# P1.net
KiCad netlist of a schematic drawn in Altium Designer
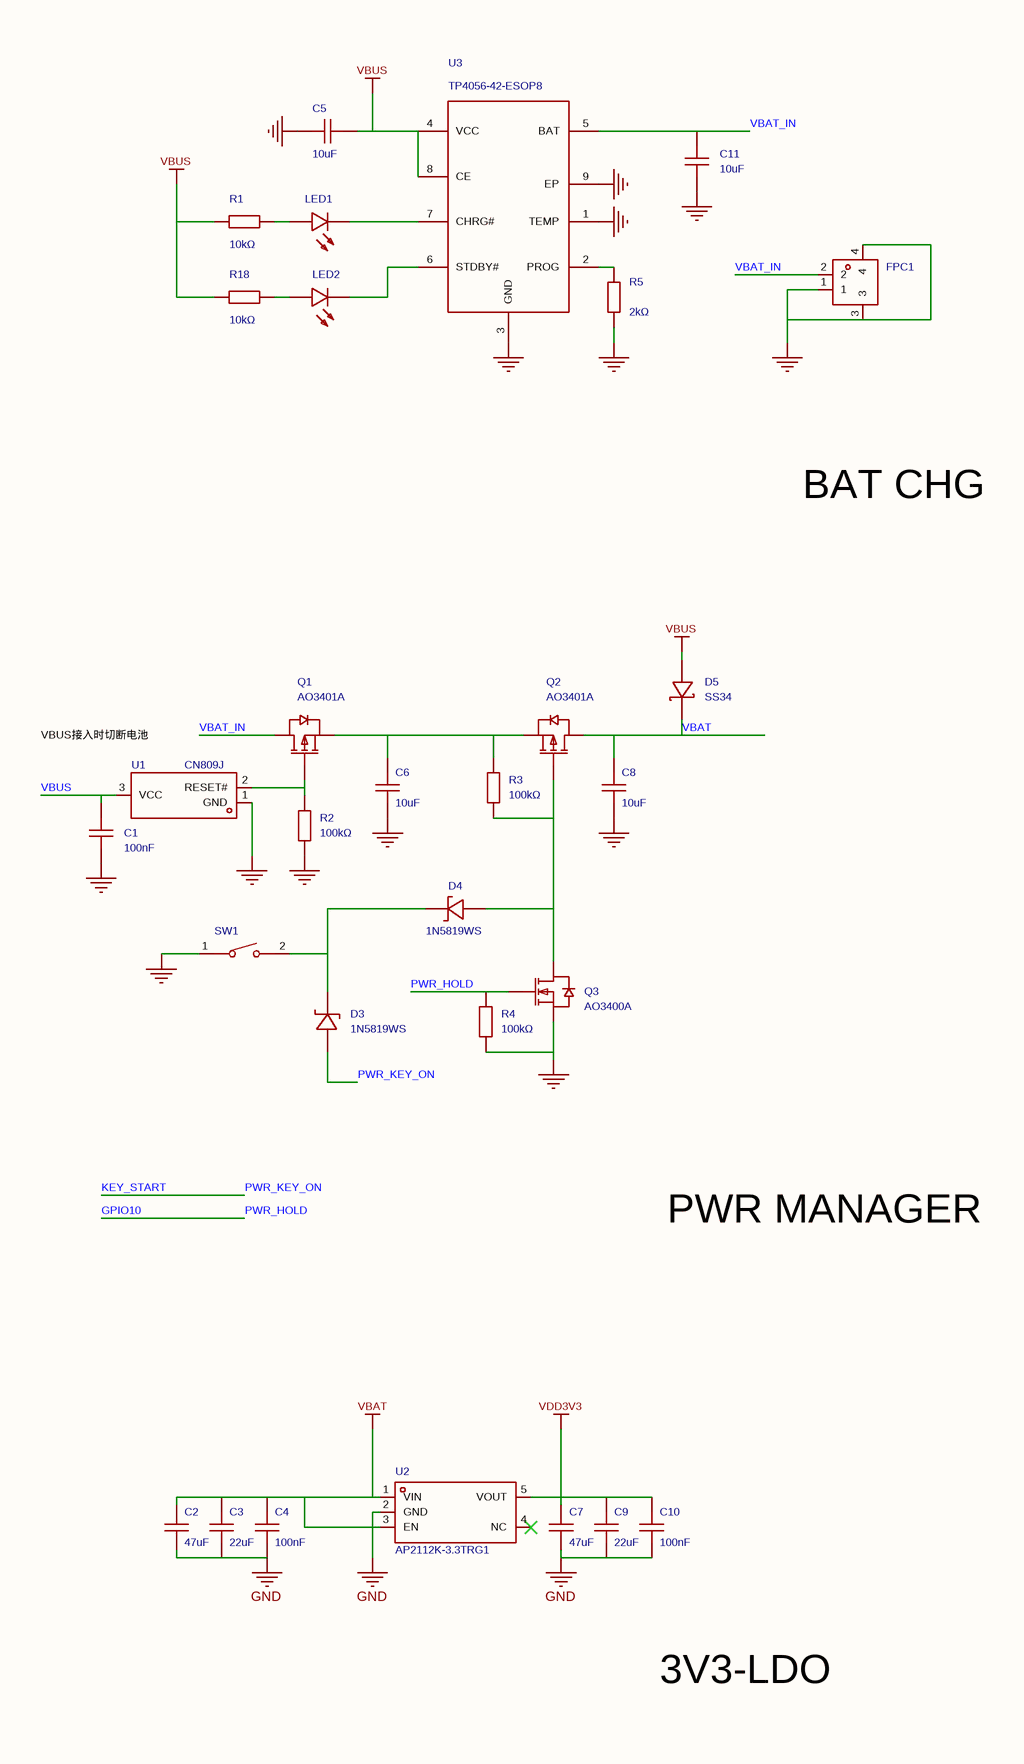
[diagram p0: P1.schdoc, left]
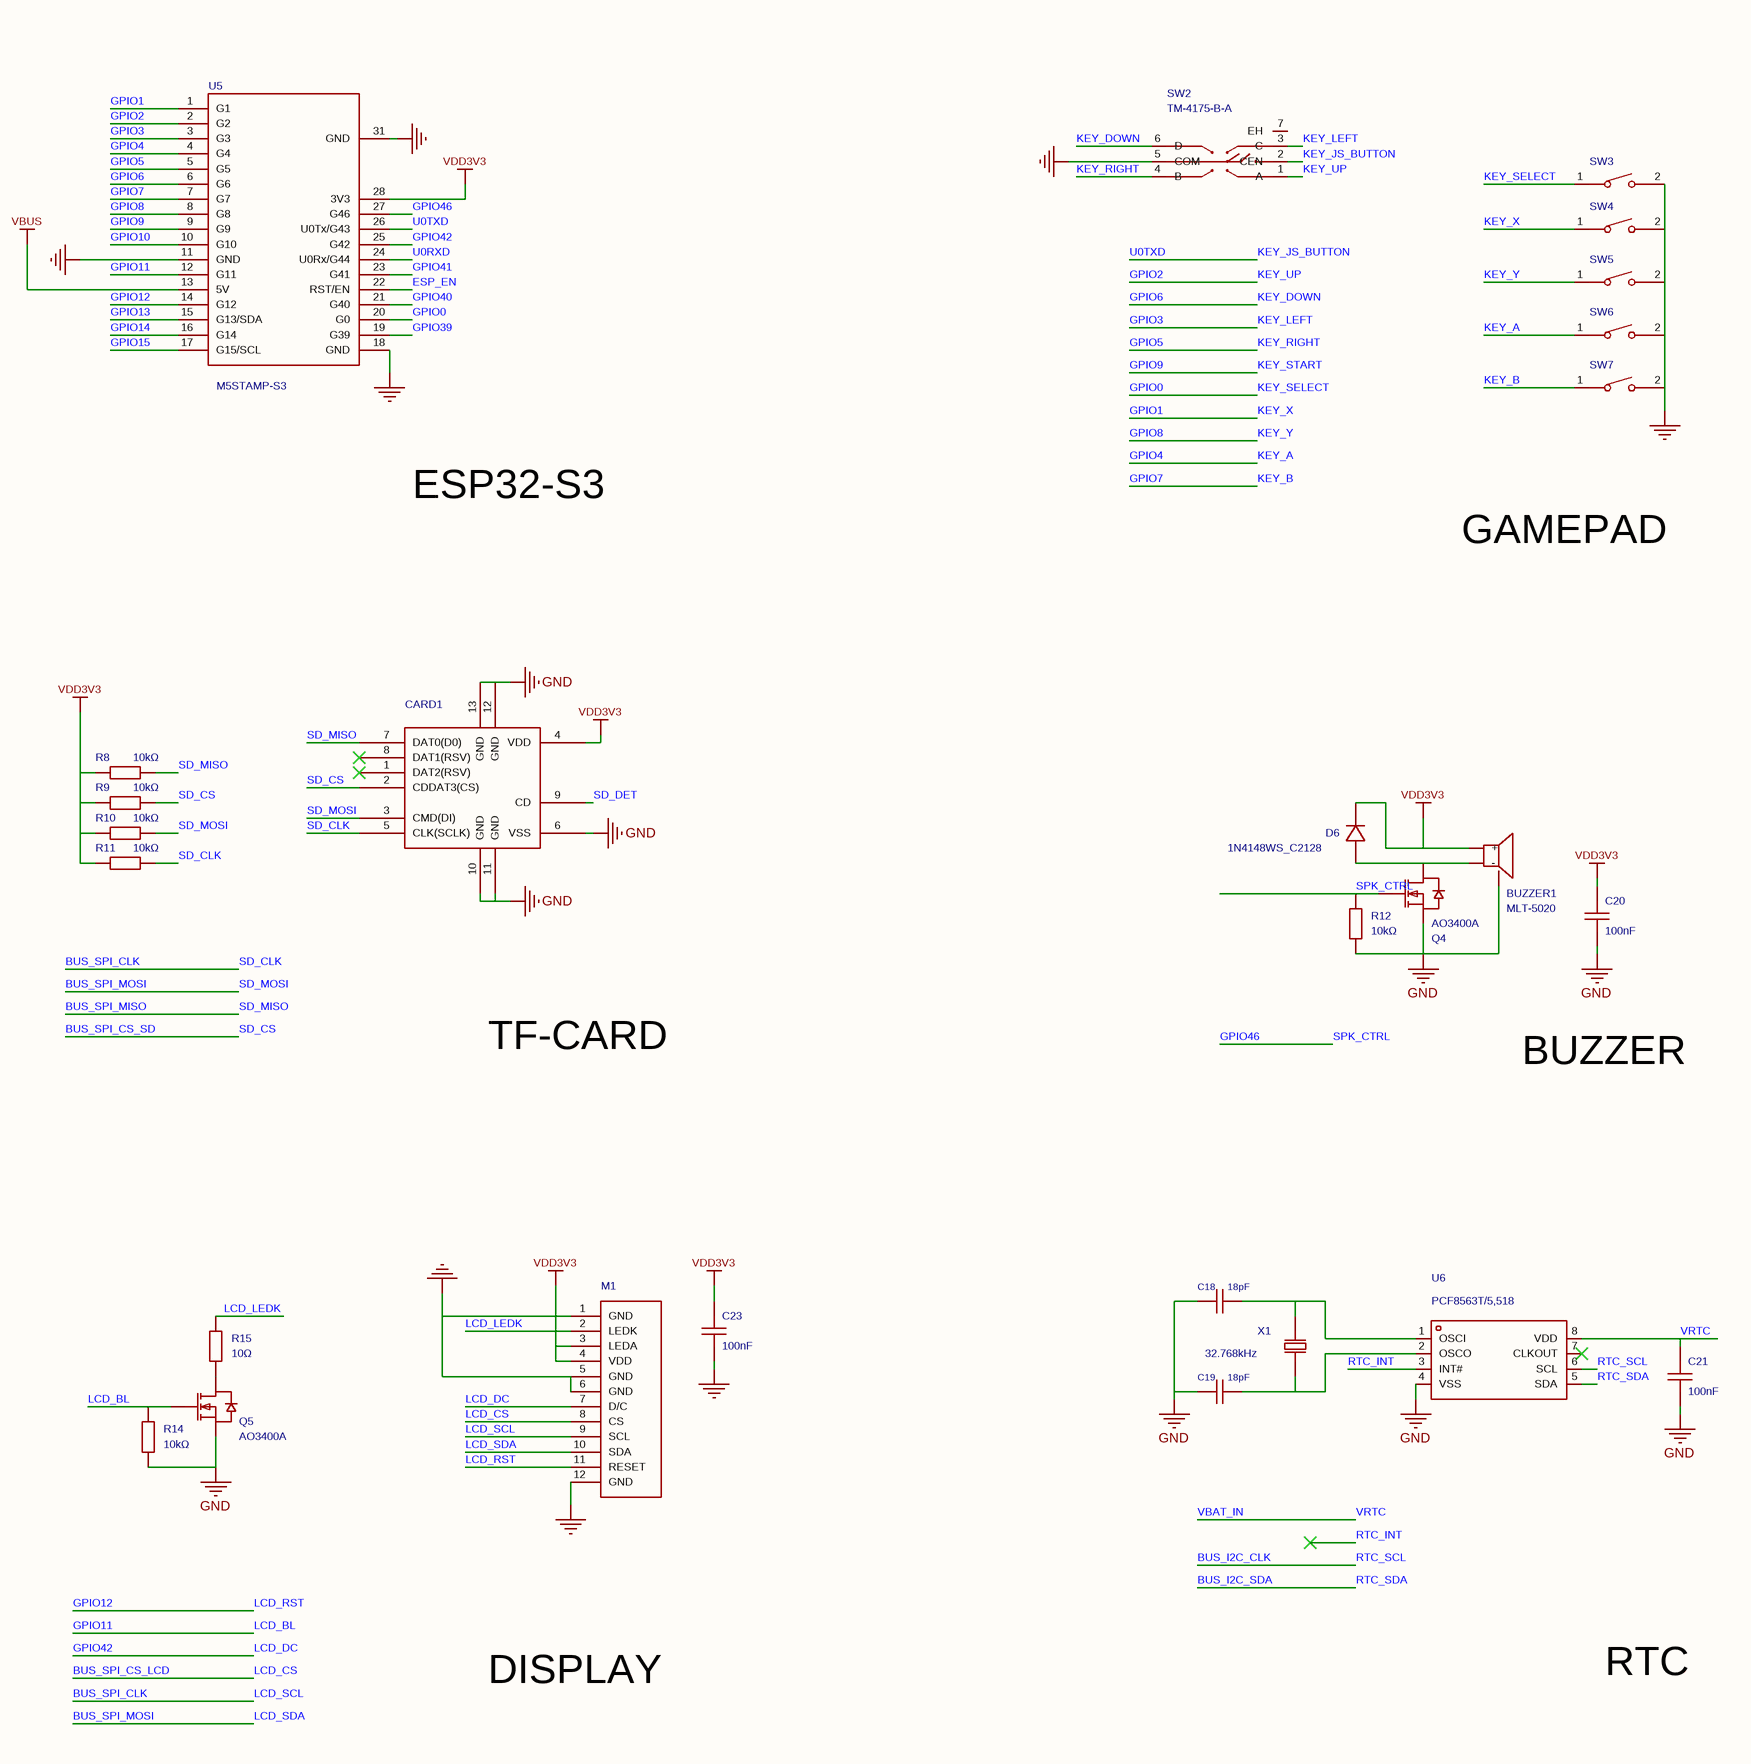
[diagram p1: P1.schdoc, middle]
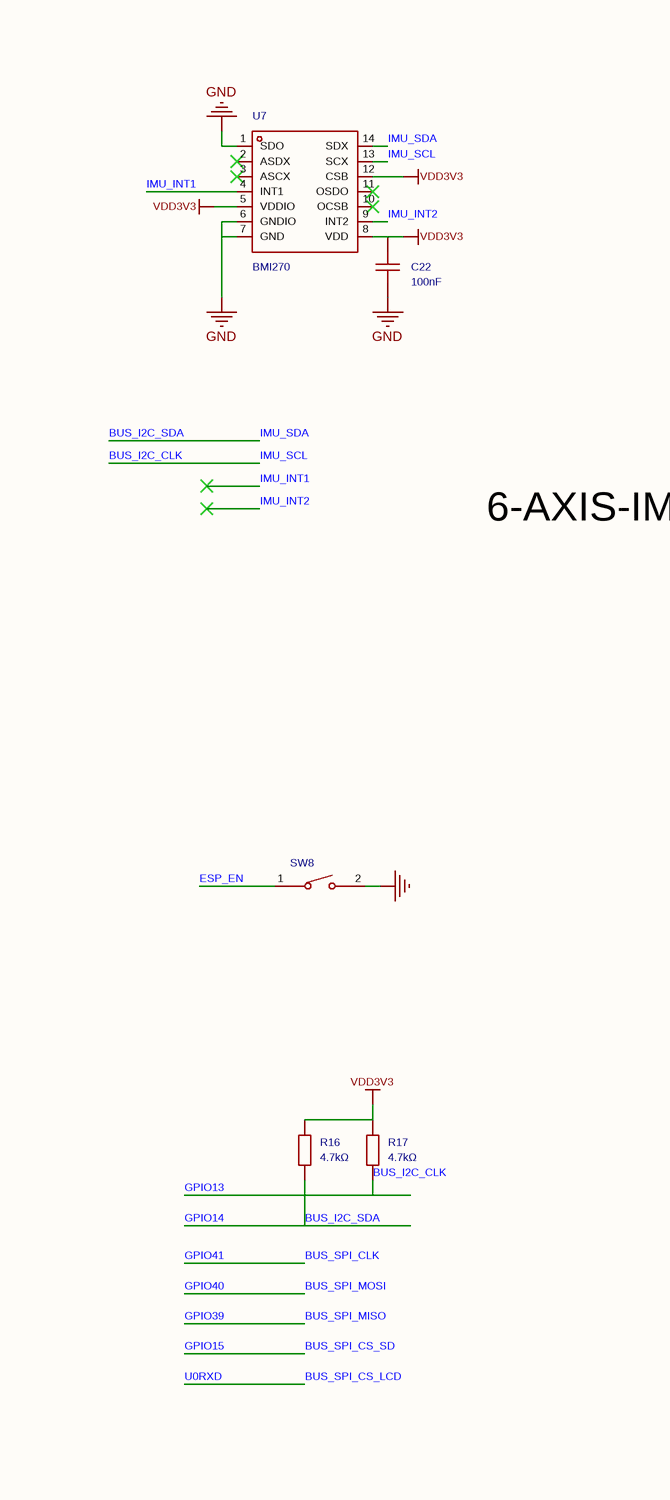
[diagram p2: P1.schdoc, right]

(export (version "E")
  (design (tool "Eeschema 10.0.6"))
  (components
    (comp (ref "BUZZER1")
      (value "4000Hz")
      (footprint "BUZ-SMD_L5.0-W5.5-P4.60")
      (description "驱动方式:无源(外部驱动);构造类型:电磁式;频率:4000Hz;长度:5.2mm;宽度:5.2mm;高度:2.5mm;")
      (fields
        (field (name "DEVICE") "MLT-5020")
        (field (name "MANUFACTURER") "华能")
        (field (name "MANUFACTURERPART") "MLT-5020")
      )
      (libsource (lib "altium-import") (part "root_0_MLT-5020_"))
    )
    (comp (ref "C1")
      (value "100nF")
      (footprint "C0603")
      (description "容值:100nF;精度:±10%;额定电压:50V;材质(温度系数):X7R;")
      (fields (field (name "MANUFACTURER") "YAGEO(国巨)") (field (name "MANUFACTURERPART") "CC0603KRX7R9BB104"))
      (libsource (lib "altium-import") (part "root_1_CC0603KRX7R9BB104_"))
    )
    (comp (ref "C2")
      (value "47uF")
      (footprint "C0805")
      (description "容值:47uF;精度:±20%;额定电压:6.3V;材质(温度系数):X5R;")
      (fields (field (name "MANUFACTURER") "SAMSUNG(三星)") (field (name "MANUFACTURERPART") "CL21A476MQYNNNE"))
      (libsource (lib "altium-import") (part "root_1_CL21A476MQYNNNE_"))
    )
    (comp (ref "C3")
      (value "22uF")
      (footprint "C0805")
      (description "容值:22uF;精度:±20%;额定电压:25V;材质(温度系数):X5R;")
      (fields (field (name "MANUFACTURER") "SAMSUNG(三星)") (field (name "MANUFACTURERPART") "CL21A226MAQNNNE"))
      (libsource (lib "altium-import") (part "root_1_CL21A226MAQNNNE_C45783_"))
    )
    (comp (ref "C4")
      (value "100nF")
      (footprint "C0603")
      (description "容值:100nF;精度:±10%;额定电压:50V;材质(温度系数):X7R;")
      (fields (field (name "MANUFACTURER") "YAGEO(国巨)") (field (name "MANUFACTURERPART") "CC0603KRX7R9BB104"))
      (libsource (lib "altium-import") (part "root_1_CC0603KRX7R9BB104_"))
    )
    (comp (ref "C5")
      (value "10uF")
      (footprint "C0603")
      (description "容值:10uF;精度:±10%;额定电压:10V;材质(温度系数):X5R;")
      (fields (field (name "MANUFACTURER") "SAMSUNG(三星)") (field (name "MANUFACTURERPART") "CL10A106KP8NNNC"))
      (libsource (lib "altium-import") (part "root_2_CL10A106KP8NNNC_"))
    )
    (comp (ref "C6")
      (value "10uF")
      (footprint "C0603")
      (description "容值:10uF;精度:±10%;额定电压:10V;材质(温度系数):X5R;")
      (fields (field (name "MANUFACTURER") "SAMSUNG(三星)") (field (name "MANUFACTURERPART") "CL10A106KP8NNNC"))
      (libsource (lib "altium-import") (part "root_1_CL10A106KP8NNNC_"))
    )
    (comp (ref "C7")
      (value "47uF")
      (footprint "C0805")
      (description "容值:47uF;精度:±20%;额定电压:6.3V;材质(温度系数):X5R;")
      (fields (field (name "MANUFACTURER") "SAMSUNG(三星)") (field (name "MANUFACTURERPART") "CL21A476MQYNNNE"))
      (libsource (lib "altium-import") (part "root_1_CL21A476MQYNNNE_"))
    )
    (comp (ref "C8")
      (value "10uF")
      (footprint "C0603")
      (description "容值:10uF;精度:±10%;额定电压:10V;材质(温度系数):X5R;")
      (fields (field (name "MANUFACTURER") "SAMSUNG(三星)") (field (name "MANUFACTURERPART") "CL10A106KP8NNNC"))
      (libsource (lib "altium-import") (part "root_1_CL10A106KP8NNNC_"))
    )
    (comp (ref "C9")
      (value "22uF")
      (footprint "C0805")
      (description "容值:22uF;精度:±20%;额定电压:25V;材质(温度系数):X5R;")
      (fields (field (name "MANUFACTURER") "SAMSUNG(三星)") (field (name "MANUFACTURERPART") "CL21A226MAQNNNE"))
      (libsource (lib "altium-import") (part "root_1_CL21A226MAQNNNE_C45783_"))
    )
    (comp (ref "C10")
      (value "100nF")
      (footprint "C0603")
      (description "容值:100nF;精度:±10%;额定电压:50V;材质(温度系数):X7R;")
      (fields (field (name "MANUFACTURER") "YAGEO(国巨)") (field (name "MANUFACTURERPART") "CC0603KRX7R9BB104"))
      (libsource (lib "altium-import") (part "root_1_CC0603KRX7R9BB104_"))
    )
    (comp (ref "C11")
      (value "10uF")
      (footprint "C0603")
      (description "容值:10uF;精度:±10%;额定电压:10V;材质(温度系数):X5R;")
      (fields (field (name "MANUFACTURER") "SAMSUNG(三星)") (field (name "MANUFACTURERPART") "CL10A106KP8NNNC"))
      (libsource (lib "altium-import") (part "root_1_CL10A106KP8NNNC_"))
    )
    (comp (ref "C18")
      (value "18pF")
      (footprint "C0603")
      (description "温度系数:C0G;容值:18pF;精度:±5%;额定电压:50V;")
      (fields
        (field (name "MANUFACTURER PART") "CL10C180JB8NNNC")
        (field (name "MANUFACTURER") "SAMSUNG(三星)")
      )
      (libsource (lib "altium-import") (part "root_0_CL10C180JB8NNNC_"))
    )
    (comp (ref "C19")
      (value "18pF")
      (footprint "C0603")
      (description "温度系数:C0G;容值:18pF;精度:±5%;额定电压:50V;")
      (fields
        (field (name "MANUFACTURER PART") "CL10C180JB8NNNC")
        (field (name "MANUFACTURER") "SAMSUNG(三星)")
      )
      (libsource (lib "altium-import") (part "root_0_CL10C180JB8NNNC_"))
    )
    (comp (ref "C20")
      (value "100nF")
      (footprint "C0603")
      (description "容值:100nF;精度:±10%;额定电压:50V;材质(温度系数):X7R;")
      (fields (field (name "MANUFACTURER") "YAGEO(国巨)") (field (name "MANUFACTURERPART") "CC0603KRX7R9BB104"))
      (libsource (lib "altium-import") (part "root_1_CC0603KRX7R9BB104_"))
    )
    (comp (ref "C21")
      (value "100nF")
      (footprint "C0603")
      (description "容值:100nF;精度:±10%;额定电压:50V;材质(温度系数):X7R;")
      (fields (field (name "MANUFACTURER") "YAGEO(国巨)") (field (name "MANUFACTURERPART") "CC0603KRX7R9BB104"))
      (libsource (lib "altium-import") (part "root_1_CC0603KRX7R9BB104_"))
    )
    (comp (ref "C22")
      (value "100nF")
      (footprint "C0603")
      (description "容值:100nF;精度:±10%;额定电压:50V;材质(温度系数):X7R;")
      (fields (field (name "MANUFACTURER") "YAGEO(国巨)") (field (name "MANUFACTURERPART") "CC0603KRX7R9BB104"))
      (libsource (lib "altium-import") (part "root_1_CC0603KRX7R9BB104_"))
    )
    (comp (ref "C23")
      (value "100nF")
      (footprint "C0603")
      (description "容值:100nF;精度:±10%;额定电压:50V;材质(温度系数):X7R;")
      (fields (field (name "MANUFACTURER") "YAGEO(国巨)") (field (name "MANUFACTURERPART") "CC0603KRX7R9BB104"))
      (libsource (lib "altium-import") (part "root_1_CC0603KRX7R9BB104_"))
    )
    (comp (ref "CARD1")
      (value "~")
      (footprint "TF-SMD_TF-01A")
      (description "卡连接方式:自弹式;卡类型:MicroSD卡(TF卡);连接器类型:卡座;本体最大高度:-;触头材质:-;触头镀层:-;工作温度范围:-;焊接温度(最大值):-;")
      (fields (field (name "MANUFACTURER") "韩国韩荣") (field (name "MANUFACTURERPART") "TF-01A"))
      (libsource (lib "altium-import") (part "root_0_TF-01A_"))
    )
    (comp (ref "D3")
      (value "1N5819WS")
      (footprint "SOD-323_L1.8-W1.3-LS2.5-RD")
      (description "直流反向耐压(Vr):40V;平均整流电流(Io):1A;正向压降(Vf):600mV@1A;")
      (fields (field (name "MANUFACTURER PART") "1N5819WS") (field (name "MANUFACTURER") "Hottech(合科泰)"))
      (libsource (lib "altium-import") (part "root_3_1N5819WS_C191023_"))
    )
    (comp (ref "D4")
      (value "1N5819WS")
      (footprint "SOD-323_L1.8-W1.3-LS2.5-RD")
      (description "直流反向耐压(Vr):40V;平均整流电流(Io):1A;正向压降(Vf):600mV@1A;")
      (fields (field (name "MANUFACTURER PART") "1N5819WS") (field (name "MANUFACTURER") "Hottech(合科泰)"))
      (libsource (lib "altium-import") (part "root_0_1N5819WS_C191023_"))
    )
    (comp (ref "D5")
      (value "SS34")
      (footprint "SMA_L4.3-W2.6-LS5.2-RD")
      (description "二极管配置:独立式;直流反向耐压(Vr):40V;平均整流电流(Io):3A;正向压降(Vf):550mV@3A;")
      (fields (field (name "MANUFACTURER PART") "SS34") (field (name "MANUFACTURER") "MDD"))
      (libsource (lib "altium-import") (part "root_1_SS34_C8678_"))
    )
    (comp (ref "D6")
      (value "1N4148WS")
      (footprint "SOD-323_L1.8-W1.3-LS2.5-RD")
      (fields (field (name "DEVICE") "1N4148WS_C2128") (field (name "MANUFACTURER") "CJ(江苏长电/长晶)"))
      (libsource (lib "altium-import") (part "root_3_1N4148WS_C2128_"))
    )
    (comp (ref "FPC1")
      (value "1.25-2PWB")
      (footprint "CONN-SMD_2P-P1.25_DEALON_1.25-2PWB")
      (description "参考系列:-;间距:1.25mm;插针结构:1x2P;排数:1;每排PIN数:2;行距:-;公母:公型插针;安装方式:卧贴;额定电流:-;工作温度范围:-40℃~+85℃;")
      (fields (field (name "MANUFACTURER") "DEALON(德艺隆)"))
      (libsource (lib "altium-import") (part "root_1_1.25-2PWB_"))
    )
    (comp (ref "LED1")
      (value "19-213/Y2C-CQ2R2L/3T(CY)")
      (footprint "LED0603-RD-YELLOW")
      (description "发光颜色:黄灯;二极管配置:-;主波长:585.5nm~591.5nm;色温:-;功率:60mW;安装方式:-;")
      (fields (field (name "MANUFACTURER") "EVERLIGHT(亿光)"))
      (libsource (lib "altium-import") (part "root_2_19-213/Y2C-CQ2R2L/3T(CY)_"))
    )
    (comp (ref "LED2")
      (value "19-217/GHC-YR1S2/3T")
      (footprint "LED0603-RD")
      (fields (field (name "MANUFACTURER") "EVERLIGHT(亿光)"))
      (libsource (lib "altium-import") (part "root_2_19-217/GHC-YR1S2/3T_"))
    )
    (comp (ref "M1")
      (value "1.3寸TFT240*240")
      (footprint "1.3寸TFT240_240")
      (libsource (lib "altium-import") (part "root_0_1.3寸TFT240*240_"))
    )
    (comp (ref "Q1")
      (value "AO3401A")
      (footprint "SOT-23_L2.9-W1.3-P1.90-LS2.4-BR")
      (description "类型:P沟道;漏源电压(Vdss):30V;连续漏极电流(Id):4A;功率(Pd):1.4W;导通电阻(RDS(on)@Vgs,Id):44mΩ@10V,4.3A;")
      (fields (field (name "MANUFACTURER PART") "AO3401A") (field (name "MANUFACTURER") "AOS"))
      (libsource (lib "altium-import") (part "root_1_AO3401A_C15127_"))
    )
    (comp (ref "Q2")
      (value "AO3401A")
      (footprint "SOT-23_L2.9-W1.3-P1.90-LS2.4-BR")
      (description "类型:P沟道;漏源电压(Vdss):30V;连续漏极电流(Id):4A;功率(Pd):1.4W;导通电阻(RDS(on)@Vgs,Id):44mΩ@10V,4.3A;")
      (fields (field (name "MANUFACTURER PART") "AO3401A") (field (name "MANUFACTURER") "AOS"))
      (libsource (lib "altium-import") (part "root_1_mirrored_AO3401A_C15127_"))
    )
    (comp (ref "Q3")
      (value "AO3400A")
      (footprint "sot-23_l2.9-w1.3-p1.90-ls2.4-br")
      (description "类型:N沟道;漏源电压(Vdss):30V;连续漏极电流(Id):5.7A;功率(Pd):1.4W;导通电阻(RDS(on)@Vgs,Id):26.5mΩ@10V,5.7A;")
      (fields (field (name "MANUFACTURER PART") "AO3400A") (field (name "MANUFACTURER") "AOS"))
      (libsource (lib "altium-import") (part "root_0_AO3400A_C20917_"))
    )
    (comp (ref "Q4")
      (value "AO3400A")
      (footprint "sot-23_l2.9-w1.3-p1.90-ls2.4-br")
      (description "类型:N沟道;漏源电压(Vdss):30V;连续漏极电流(Id):5.7A;功率(Pd):1.4W;导通电阻(RDS(on)@Vgs,Id):26.5mΩ@10V,5.7A;")
      (fields (field (name "MANUFACTURER PART") "AO3400A") (field (name "MANUFACTURER") "AOS"))
      (libsource (lib "altium-import") (part "root_0_AO3400A_C20917_"))
    )
    (comp (ref "Q5")
      (value "AO3400A")
      (footprint "sot-23_l2.9-w1.3-p1.90-ls2.4-br")
      (description "类型:N沟道;漏源电压(Vdss):30V;连续漏极电流(Id):5.7A;功率(Pd):1.4W;导通电阻(RDS(on)@Vgs,Id):26.5mΩ@10V,5.7A;")
      (fields (field (name "MANUFACTURER PART") "AO3400A") (field (name "MANUFACTURER") "AOS"))
      (libsource (lib "altium-import") (part "root_0_AO3400A_C20917_"))
    )
    (comp (ref "R1")
      (value "10kΩ")
      (footprint "R0603")
      (description "电阻类型:厚膜电阻;阻值:10kΩ;精度:±1%;功率:100mW;")
      (fields
        (field (name "MANUFACTURER") "UNI-ROYAL(厚声)")
        (field (name "MANUFACTURERPART") "0603WAF1002T5E")
      )
      (libsource (lib "altium-import") (part "root_0_0603WAF1002T5E_"))
    )
    (comp (ref "R2")
      (value "100kΩ")
      (footprint "R0603")
      (description "电阻类型:厚膜电阻;阻值:100kΩ;精度:±1%;功率:100mW;")
      (fields
        (field (name "MANUFACTURER") "UNI-ROYAL(厚声)")
        (field (name "MANUFACTURERPART") "0603WAF1003T5E")
      )
      (libsource (lib "altium-import") (part "root_1_0603WAF1003T5E_"))
    )
    (comp (ref "R3")
      (value "100kΩ")
      (footprint "R0603")
      (description "电阻类型:厚膜电阻;阻值:100kΩ;精度:±1%;功率:100mW;")
      (fields
        (field (name "MANUFACTURER") "UNI-ROYAL(厚声)")
        (field (name "MANUFACTURERPART") "0603WAF1003T5E")
      )
      (libsource (lib "altium-import") (part "root_1_0603WAF1003T5E_"))
    )
    (comp (ref "R4")
      (value "100kΩ")
      (footprint "R0603")
      (description "电阻类型:厚膜电阻;阻值:100kΩ;精度:±1%;功率:100mW;")
      (fields
        (field (name "MANUFACTURER") "UNI-ROYAL(厚声)")
        (field (name "MANUFACTURERPART") "0603WAF1003T5E")
      )
      (libsource (lib "altium-import") (part "root_1_0603WAF1003T5E_"))
    )
    (comp (ref "R5")
      (value "2kΩ")
      (footprint "R0603")
      (description "电阻类型:厚膜电阻;阻值:2kΩ;精度:±1%;功率:100mW;")
      (fields
        (field (name "MANUFACTURER") "UNI-ROYAL(厚声)")
        (field (name "MANUFACTURERPART") "0603WAF2001T5E")
      )
      (libsource (lib "altium-import") (part "root_1_0603WAF2001T5E_"))
    )
    (comp (ref "R8")
      (value "10kΩ")
      (footprint "R0603")
      (description "电阻类型:厚膜电阻;阻值:10kΩ;精度:±1%;功率:100mW;")
      (fields
        (field (name "MANUFACTURER") "UNI-ROYAL(厚声)")
        (field (name "MANUFACTURERPART") "0603WAF1002T5E")
      )
      (libsource (lib "altium-import") (part "root_2_0603WAF1002T5E_"))
    )
    (comp (ref "R9")
      (value "10kΩ")
      (footprint "R0603")
      (description "电阻类型:厚膜电阻;阻值:10kΩ;精度:±1%;功率:100mW;")
      (fields
        (field (name "MANUFACTURER") "UNI-ROYAL(厚声)")
        (field (name "MANUFACTURERPART") "0603WAF1002T5E")
      )
      (libsource (lib "altium-import") (part "root_2_0603WAF1002T5E_"))
    )
    (comp (ref "R10")
      (value "10kΩ")
      (footprint "R0603")
      (description "电阻类型:厚膜电阻;阻值:10kΩ;精度:±1%;功率:100mW;")
      (fields
        (field (name "MANUFACTURER") "UNI-ROYAL(厚声)")
        (field (name "MANUFACTURERPART") "0603WAF1002T5E")
      )
      (libsource (lib "altium-import") (part "root_2_0603WAF1002T5E_"))
    )
    (comp (ref "R11")
      (value "10kΩ")
      (footprint "R0603")
      (description "电阻类型:厚膜电阻;阻值:10kΩ;精度:±1%;功率:100mW;")
      (fields
        (field (name "MANUFACTURER") "UNI-ROYAL(厚声)")
        (field (name "MANUFACTURERPART") "0603WAF1002T5E")
      )
      (libsource (lib "altium-import") (part "root_2_0603WAF1002T5E_"))
    )
    (comp (ref "R12")
      (value "10kΩ")
      (footprint "R0603")
      (description "电阻类型:厚膜电阻;阻值:10kΩ;精度:±1%;功率:100mW;")
      (fields
        (field (name "MANUFACTURER") "UNI-ROYAL(厚声)")
        (field (name "MANUFACTURERPART") "0603WAF1002T5E")
      )
      (libsource (lib "altium-import") (part "root_3_0603WAF1002T5E_"))
    )
    (comp (ref "R14")
      (value "10kΩ")
      (footprint "R0603")
      (description "电阻类型:厚膜电阻;阻值:10kΩ;精度:±1%;功率:100mW;")
      (fields
        (field (name "MANUFACTURER") "UNI-ROYAL(厚声)")
        (field (name "MANUFACTURERPART") "0603WAF1002T5E")
      )
      (libsource (lib "altium-import") (part "root_3_0603WAF1002T5E_"))
    )
    (comp (ref "R15")
      (value "10Ω")
      (footprint "R0603")
      (description "电阻类型:厚膜电阻;阻值:10Ω;精度:±1%;功率:100mW;温度系数:±400ppm/℃;最大工作电压:75V;工作温度范围:-55℃~+155℃;")
      (fields
        (field (name "MANUFACTURER") "UNI-ROYAL(厚声)")
        (field (name "MANUFACTURERPART") "0603WAF100JT5E")
      )
      (libsource (lib "altium-import") (part "root_1_0603WAF100JT5E_"))
    )
    (comp (ref "R16")
      (value "4.7kΩ")
      (footprint "R0603")
      (description "电阻类型:厚膜电阻;阻值:4.7kΩ;精度:±1%;功率:100mW;")
      (fields
        (field (name "MANUFACTURER") "UNI-ROYAL(厚声)")
        (field (name "MANUFACTURERPART") "0603WAF4701T5E")
      )
      (libsource (lib "altium-import") (part "root_1_0603WAF4701T5E_"))
    )
    (comp (ref "R17")
      (value "4.7kΩ")
      (footprint "R0603")
      (description "电阻类型:厚膜电阻;阻值:4.7kΩ;精度:±1%;功率:100mW;")
      (fields
        (field (name "MANUFACTURER") "UNI-ROYAL(厚声)")
        (field (name "MANUFACTURERPART") "0603WAF4701T5E")
      )
      (libsource (lib "altium-import") (part "root_1_0603WAF4701T5E_"))
    )
    (comp (ref "R18")
      (value "10kΩ")
      (footprint "R0603")
      (description "电阻类型:厚膜电阻;阻值:10kΩ;精度:±1%;功率:100mW;")
      (fields
        (field (name "MANUFACTURER") "UNI-ROYAL(厚声)")
        (field (name "MANUFACTURERPART") "0603WAF1002T5E")
      )
      (libsource (lib "altium-import") (part "root_0_0603WAF1002T5E_"))
    )
    (comp (ref "SW1")
      (value "TS-1088-AR02016")
      (footprint "SW-SMD_L3.9-W3.0-P4.45")
      (description "触点电流:50mA;额定电压(DC):12V;绝缘电阻:100MΩ;电路结构:单刀单掷;安装方式:立贴;作用力:160gf@±50gf;机械寿命:10万次;带支架:否;")
      (fields (field (name "MANUFACTURER") "XUNPU(讯普)"))
      (libsource (lib "altium-import") (part "root_0_TS-1088-AR02016_"))
    )
    (comp (ref "SW2")
      (value "TM-4175-B-A")
      (footprint "SW-SMD_TM-4175-B-X")
      (description "多功能开关 7.5*7.5*5 五向开关 H5")
      (fields (field (name "MANUFACTURER") "XKB Connectivity(中国星坤)") (field (name "DEVICE") "TM-4175-B-A"))
      (libsource (lib "altium-import") (part "root_0_TM-4175-B-A_"))
    )
    (comp (ref "SW3")
      (value "TS-1088-AR02016")
      (footprint "SW-SMD_L3.9-W3.0-P4.45")
      (description "触点电流:50mA;额定电压(DC):12V;绝缘电阻:100MΩ;电路结构:单刀单掷;安装方式:立贴;作用力:160gf@±50gf;机械寿命:10万次;带支架:否;")
      (fields (field (name "MANUFACTURER") "XUNPU(讯普)"))
      (libsource (lib "altium-import") (part "root_0_TS-1088-AR02016_"))
    )
    (comp (ref "SW4")
      (value "TS-1088-AR02016")
      (footprint "SW-SMD_L3.9-W3.0-P4.45")
      (description "触点电流:50mA;额定电压(DC):12V;绝缘电阻:100MΩ;电路结构:单刀单掷;安装方式:立贴;作用力:160gf@±50gf;机械寿命:10万次;带支架:否;")
      (fields (field (name "MANUFACTURER") "XUNPU(讯普)"))
      (libsource (lib "altium-import") (part "root_0_TS-1088-AR02016_"))
    )
    (comp (ref "SW5")
      (value "TS-1088-AR02016")
      (footprint "SW-SMD_L3.9-W3.0-P4.45")
      (description "触点电流:50mA;额定电压(DC):12V;绝缘电阻:100MΩ;电路结构:单刀单掷;安装方式:立贴;作用力:160gf@±50gf;机械寿命:10万次;带支架:否;")
      (fields (field (name "MANUFACTURER") "XUNPU(讯普)"))
      (libsource (lib "altium-import") (part "root_0_TS-1088-AR02016_"))
    )
    (comp (ref "SW6")
      (value "TS-1088-AR02016")
      (footprint "SW-SMD_L3.9-W3.0-P4.45")
      (description "触点电流:50mA;额定电压(DC):12V;绝缘电阻:100MΩ;电路结构:单刀单掷;安装方式:立贴;作用力:160gf@±50gf;机械寿命:10万次;带支架:否;")
      (fields (field (name "MANUFACTURER") "XUNPU(讯普)"))
      (libsource (lib "altium-import") (part "root_0_TS-1088-AR02016_"))
    )
    (comp (ref "SW7")
      (value "TS-1088-AR02016")
      (footprint "SW-SMD_L3.9-W3.0-P4.45")
      (description "触点电流:50mA;额定电压(DC):12V;绝缘电阻:100MΩ;电路结构:单刀单掷;安装方式:立贴;作用力:160gf@±50gf;机械寿命:10万次;带支架:否;")
      (fields (field (name "MANUFACTURER") "XUNPU(讯普)"))
      (libsource (lib "altium-import") (part "root_0_TS-1088-AR02016_"))
    )
    (comp (ref "SW8")
      (value "TS-1088-AR02016")
      (footprint "SW-SMD_L3.9-W3.0-P4.45")
      (description "触点电流:50mA;额定电压(DC):12V;绝缘电阻:100MΩ;电路结构:单刀单掷;安装方式:立贴;作用力:160gf@±50gf;机械寿命:10万次;带支架:否;")
      (fields (field (name "MANUFACTURER") "XUNPU(讯普)"))
      (libsource (lib "altium-import") (part "root_0_TS-1088-AR02016_"))
    )
    (comp (ref "U1")
      (value "CN809J")
      (footprint "SOT-23-3_L2.9-W1.3-P1.90-LS2.4-BR")
      (description "电源管理芯片的类型:-;监控的组数:-;输出端类型:-;有效的复位电平:-;复位阀值电压:-;")
      (fields (field (name "DEVICE") "CN809J") (field (name "MANUFACTURER") "CONSONANCE(上海如韵)"))
      (libsource (lib "altium-import") (part "root_2_CN809J_"))
    )
    (comp (ref "U2")
      (value "AP2112K-3.3TRG1")
      (footprint "SOT-25-5_L3.0-W1.8-P0.95-LS3.0-BR")
      (fields (field (name "MANUFACTURER PART") "AP2112K-3.3TRG1") (field (name "MANUFACTURER") "DIODES(美台)"))
      (libsource (lib "altium-import") (part "root_0_AP2112K-3.3TRG1_"))
    )
    (comp (ref "U3")
      (value "TP4056-42-ESOP8")
      (footprint "ESOP-8_L4.9-W3.9-P1.27-LS6.0-BL-EP")
      (description "锂电池充电芯片")
      (fields (field (name "DEVICE") "TP4056-42-ESOP8") (field (name "MANUFACTURER") "TOPPOWER(南京拓微)"))
      (libsource (lib "altium-import") (part "root_0_TP4056-42-ESOP8_"))
    )
    (comp (ref "U5")
      (value "M5STAMP-S3")
      (footprint "STAMP-S3-PIN-SMD")
      (libsource (lib "altium-import") (part "root_0_STAMP-S3-PIN-SMD_"))
    )
    (comp (ref "U6")
      (value "PCF8563T/5,518")
      (footprint "SOIC-8_L5.0-W4.0-P1.27-LS6.0-BL")
      (description "接口:I2C;")
      (fields (field (name "DEVICE") "PCF8563T/5,518") (field (name "MANUFACTURER") "NXP(恩智浦)"))
      (libsource (lib "altium-import") (part "root_0_PCF8563T/5,518_"))
    )
    (comp (ref "U7")
      (value "BMI270")
      (footprint "LGA-14_L3.0-W2.5-P0.50-BR")
      (description "IMU-惯性测量单元")
      (fields (field (name "LCSC PART NAME") "BMI270") (field (name "MANUFACTURER") "Bosch(博世)"))
      (libsource (lib "altium-import") (part "root_0_BMI270_"))
    )
    (comp (ref "X1")
      (value "32.768kHz")
      (footprint "FC-135R_L3.2-W1.5")
      (description "晶振类型:贴片无源晶振;频率:32.768kHz;频率公差:±20ppm;负载电容:12.5pF;等效串联电阻(ESR):70kΩ;工作温度:-40℃~+85℃;")
      (fields (field (name "MANUFACTURER") "EPSON(爱普生)") (field (name "MANUFACTURERPART") "Q13FC1350000400"))
      (libsource (lib "altium-import") (part "root_3_Q13FC1350000400_"))
    )
  )
  (nets
    (net (code "1") (name "/BUS_I2C_CLK") (class "Default")
      (node (ref "R17") (pin "1") (pinfunction "1_1") (pintype "passive"))
      (node (ref "U5") (pin "15") (pinfunction "G13/SDA_15") (pintype "passive"))
      (node (ref "U6") (pin "6") (pinfunction "SCL_6") (pintype "passive"))
      (node (ref "U7") (pin "13") (pinfunction "SCX_13") (pintype "passive"))
    )
    (net (code "2") (name "/BUS_I2C_SDA") (class "Default")
      (node (ref "R16") (pin "1") (pinfunction "1_1") (pintype "passive"))
      (node (ref "U5") (pin "16") (pinfunction "G14_16") (pintype "passive"))
      (node (ref "U6") (pin "5") (pinfunction "SDA_5") (pintype "passive"))
      (node (ref "U7") (pin "14") (pinfunction "SDX_14") (pintype "passive"))
    )
    (net (code "3") (name "/BUS_SPI_CLK") (class "Default")
      (node (ref "CARD1") (pin "5") (pinfunction "CLK(SCLK)_5") (pintype "passive"))
      (node (ref "M1") (pin "9") (pinfunction "SCL_9") (pintype "passive"))
      (node (ref "R11") (pin "1") (pinfunction "1_1") (pintype "passive"))
      (node (ref "U5") (pin "23") (pinfunction "G41_23") (pintype "passive"))
    )
    (net (code "4") (name "/BUS_SPI_CS_LCD") (class "Default")
      (node (ref "M1") (pin "8") (pinfunction "CS_8") (pintype "passive"))
      (node (ref "U5") (pin "24") (pinfunction "U0Rx/G44_24") (pintype "passive"))
    )
    (net (code "5") (name "/BUS_SPI_CS_SD") (class "Default")
      (node (ref "CARD1") (pin "2") (pinfunction "CDDAT3(CS)_2") (pintype "passive"))
      (node (ref "R9") (pin "1") (pinfunction "1_1") (pintype "passive"))
      (node (ref "U5") (pin "17") (pinfunction "G15/SCL_17") (pintype "passive"))
    )
    (net (code "6") (name "/BUS_SPI_MISO") (class "Default")
      (node (ref "CARD1") (pin "7") (pinfunction "DAT0(D0)_7") (pintype "passive"))
      (node (ref "R8") (pin "1") (pinfunction "1_1") (pintype "passive"))
      (node (ref "U5") (pin "19") (pinfunction "G39_19") (pintype "passive"))
    )
    (net (code "7") (name "/BUS_SPI_MOSI") (class "Default")
      (node (ref "CARD1") (pin "3") (pinfunction "CMD(DI)_3") (pintype "passive"))
      (node (ref "M1") (pin "10") (pinfunction "SDA_10") (pintype "passive"))
      (node (ref "R10") (pin "1") (pinfunction "1_1") (pintype "passive"))
      (node (ref "U5") (pin "21") (pinfunction "G40_21") (pintype "passive"))
    )
    (net (code "8") (name "/ESP_EN") (class "Default")
      (node (ref "SW8") (pin "1") (pinfunction "1_1") (pintype "passive"))
      (node (ref "U5") (pin "22") (pinfunction "RST/EN_22") (pintype "passive"))
    )
    (net (code "9") (name "/GPIO0") (class "Default")
      (node (ref "SW3") (pin "1") (pinfunction "1_1") (pintype "passive"))
      (node (ref "U5") (pin "20") (pinfunction "G0_20") (pintype "passive"))
    )
    (net (code "10") (name "/GPIO1") (class "Default")
      (node (ref "SW4") (pin "1") (pinfunction "1_1") (pintype "passive"))
      (node (ref "U5") (pin "1") (pinfunction "G1_1") (pintype "passive"))
    )
    (net (code "11") (name "/GPIO2") (class "Default")
      (node (ref "SW2") (pin "1") (pinfunction "A_1") (pintype "passive"))
      (node (ref "U5") (pin "2") (pinfunction "G2_2") (pintype "passive"))
    )
    (net (code "12") (name "/GPIO3") (class "Default")
      (node (ref "SW2") (pin "3") (pinfunction "C_3") (pintype "passive"))
      (node (ref "U5") (pin "3") (pinfunction "G3_3") (pintype "passive"))
    )
    (net (code "13") (name "/GPIO4") (class "Default")
      (node (ref "SW6") (pin "1") (pinfunction "1_1") (pintype "passive"))
      (node (ref "U5") (pin "4") (pinfunction "G4_4") (pintype "passive"))
    )
    (net (code "14") (name "/GPIO5") (class "Default")
      (node (ref "SW2") (pin "4") (pinfunction "B_4") (pintype "passive"))
      (node (ref "U5") (pin "5") (pinfunction "G5_5") (pintype "passive"))
    )
    (net (code "15") (name "/GPIO6") (class "Default")
      (node (ref "SW2") (pin "6") (pinfunction "D_6") (pintype "passive"))
      (node (ref "U5") (pin "6") (pinfunction "G6_6") (pintype "passive"))
    )
    (net (code "16") (name "/GPIO7") (class "Default")
      (node (ref "SW7") (pin "1") (pinfunction "1_1") (pintype "passive"))
      (node (ref "U5") (pin "7") (pinfunction "G7_7") (pintype "passive"))
    )
    (net (code "17") (name "/GPIO8") (class "Default")
      (node (ref "SW5") (pin "1") (pinfunction "1_1") (pintype "passive"))
      (node (ref "U5") (pin "8") (pinfunction "G8_8") (pintype "passive"))
    )
    (net (code "18") (name "/GPIO9") (class "Default")
      (node (ref "D3") (pin "2") (pinfunction "A_2") (pintype "passive"))
      (node (ref "U5") (pin "9") (pinfunction "G9_9") (pintype "passive"))
    )
    (net (code "19") (name "/GPIO10") (class "Default")
      (node (ref "Q3") (pin "1") (pinfunction "G_1") (pintype "passive"))
      (node (ref "R4") (pin "2") (pinfunction "2_2") (pintype "passive"))
      (node (ref "U5") (pin "10") (pinfunction "G10_10") (pintype "passive"))
    )
    (net (code "20") (name "/GPIO11") (class "Default")
      (node (ref "Q5") (pin "1") (pinfunction "G_1") (pintype "passive"))
      (node (ref "R14") (pin "1") (pinfunction "1_1") (pintype "passive"))
      (node (ref "U5") (pin "12") (pinfunction "G11_12") (pintype "passive"))
    )
    (net (code "21") (name "/GPIO12") (class "Default")
      (node (ref "M1") (pin "11") (pinfunction "RESET_11") (pintype "passive"))
      (node (ref "U5") (pin "14") (pinfunction "G12_14") (pintype "passive"))
    )
    (net (code "22") (name "/GPIO42") (class "Default")
      (node (ref "M1") (pin "7") (pinfunction "D/C_7") (pintype "passive"))
      (node (ref "U5") (pin "25") (pinfunction "G42_25") (pintype "passive"))
    )
    (net (code "23") (name "/GPIO46") (class "Default")
      (node (ref "Q4") (pin "1") (pinfunction "G_1") (pintype "passive"))
      (node (ref "R12") (pin "1") (pinfunction "1_1") (pintype "passive"))
      (node (ref "U5") (pin "27") (pinfunction "G46_27") (pintype "passive"))
    )
    (net (code "24") (name "/IMU_INT1") (class "Default")
      (node (ref "U7") (pin "4") (pinfunction "INT1_4") (pintype "passive+no_connect"))
    )
    (net (code "25") (name "/IMU_INT2") (class "Default")
      (node (ref "U7") (pin "9") (pinfunction "INT2_9") (pintype "passive+no_connect"))
    )
    (net (code "26") (name "/KEY_JS_BUTTON") (class "Default")
      (node (ref "SW2") (pin "2") (pinfunction "CEN_2") (pintype "passive"))
      (node (ref "U5") (pin "26") (pinfunction "U0Tx/G43_26") (pintype "passive"))
    )
    (net (code "27") (name "/LCD_LEDK") (class "Default")
      (node (ref "M1") (pin "2") (pinfunction "LEDK_2") (pintype "passive"))
      (node (ref "R15") (pin "2") (pinfunction "2_2") (pintype "passive"))
    )
    (net (code "28") (name "/RTC_INT") (class "Default")
      (node (ref "U6") (pin "3") (pinfunction "INT#_3") (pintype "passive+no_connect"))
    )
    (net (code "29") (name "/SD_DET") (class "Default")
      (node (ref "CARD1") (pin "9") (pinfunction "CD_9") (pintype "passive"))
    )
    (net (code "30") (name "/VBAT_IN") (class "Default")
      (node (ref "C11") (pin "2") (pinfunction "2_2") (pintype "passive"))
      (node (ref "C21") (pin "2") (pinfunction "2_2") (pintype "passive"))
      (node (ref "FPC1") (pin "2") (pinfunction "2_2") (pintype "passive"))
      (node (ref "Q1") (pin "3") (pinfunction "D_3") (pintype "passive"))
      (node (ref "U3") (pin "5") (pinfunction "BAT_5") (pintype "passive"))
      (node (ref "U6") (pin "8") (pinfunction "VDD_8") (pintype "passive"))
    )
    (net (code "31") (name "GND") (class "Default")
      (node (ref "BUZZER1") (pin "3") (pinfunction "NC_3") (pintype "passive"))
      (node (ref "C1") (pin "1") (pinfunction "1_1") (pintype "passive"))
      (node (ref "C10") (pin "1") (pinfunction "1_1") (pintype "passive"))
      (node (ref "C11") (pin "1") (pinfunction "1_1") (pintype "passive"))
      (node (ref "C18") (pin "1") (pinfunction "1_1") (pintype "passive"))
      (node (ref "C19") (pin "1") (pinfunction "1_1") (pintype "passive"))
      (node (ref "C2") (pin "1") (pinfunction "1_1") (pintype "passive"))
      (node (ref "C20") (pin "1") (pinfunction "1_1") (pintype "passive"))
      (node (ref "C21") (pin "1") (pinfunction "1_1") (pintype "passive"))
      (node (ref "C22") (pin "1") (pinfunction "1_1") (pintype "passive"))
      (node (ref "C23") (pin "1") (pinfunction "1_1") (pintype "passive"))
      (node (ref "C3") (pin "1") (pinfunction "1_1") (pintype "passive"))
      (node (ref "C4") (pin "1") (pinfunction "1_1") (pintype "passive"))
      (node (ref "C5") (pin "2") (pinfunction "2_2") (pintype "passive"))
      (node (ref "C6") (pin "1") (pinfunction "1_1") (pintype "passive"))
      (node (ref "C7") (pin "1") (pinfunction "1_1") (pintype "passive"))
      (node (ref "C8") (pin "1") (pinfunction "1_1") (pintype "passive"))
      (node (ref "C9") (pin "1") (pinfunction "1_1") (pintype "passive"))
      (node (ref "CARD1") (pin "10") (pinfunction "GND_10") (pintype "passive"))
      (node (ref "CARD1") (pin "11") (pinfunction "GND_11") (pintype "passive"))
      (node (ref "CARD1") (pin "12") (pinfunction "GND_12") (pintype "passive"))
      (node (ref "CARD1") (pin "13") (pinfunction "GND_13") (pintype "passive"))
      (node (ref "CARD1") (pin "6") (pinfunction "VSS_6") (pintype "passive"))
      (node (ref "FPC1") (pin "1") (pinfunction "1_1") (pintype "passive"))
      (node (ref "FPC1") (pin "3") (pinfunction "3_3") (pintype "passive"))
      (node (ref "FPC1") (pin "4") (pinfunction "4_4") (pintype "passive"))
      (node (ref "M1") (pin "1") (pinfunction "GND_1") (pintype "passive"))
      (node (ref "M1") (pin "12") (pinfunction "GND_12") (pintype "passive"))
      (node (ref "M1") (pin "5") (pinfunction "GND_5") (pintype "passive"))
      (node (ref "M1") (pin "6") (pinfunction "GND_6") (pintype "passive"))
      (node (ref "Q3") (pin "2") (pinfunction "S_2") (pintype "passive"))
      (node (ref "Q4") (pin "2") (pinfunction "S_2") (pintype "passive"))
      (node (ref "Q5") (pin "2") (pinfunction "S_2") (pintype "passive"))
      (node (ref "R12") (pin "2") (pinfunction "2_2") (pintype "passive"))
      (node (ref "R14") (pin "2") (pinfunction "2_2") (pintype "passive"))
      (node (ref "R2") (pin "1") (pinfunction "1_1") (pintype "passive"))
      (node (ref "R4") (pin "1") (pinfunction "1_1") (pintype "passive"))
      (node (ref "R5") (pin "1") (pinfunction "1_1") (pintype "passive"))
      (node (ref "SW1") (pin "1") (pinfunction "1_1") (pintype "passive"))
      (node (ref "SW2") (pin "5") (pinfunction "COM_5") (pintype "passive"))
      (node (ref "SW3") (pin "2") (pinfunction "2_2") (pintype "passive"))
      (node (ref "SW4") (pin "2") (pinfunction "2_2") (pintype "passive"))
      (node (ref "SW5") (pin "2") (pinfunction "2_2") (pintype "passive"))
      (node (ref "SW6") (pin "2") (pinfunction "2_2") (pintype "passive"))
      (node (ref "SW7") (pin "2") (pinfunction "2_2") (pintype "passive"))
      (node (ref "SW8") (pin "2") (pinfunction "2_2") (pintype "passive"))
      (node (ref "U1") (pin "1") (pinfunction "GND_1") (pintype "passive"))
      (node (ref "U2") (pin "2") (pinfunction "GND_2") (pintype "passive"))
      (node (ref "U3") (pin "1") (pinfunction "TEMP_1") (pintype "passive"))
      (node (ref "U3") (pin "3") (pinfunction "GND_3") (pintype "passive"))
      (node (ref "U3") (pin "9") (pinfunction "EP_9") (pintype "passive"))
      (node (ref "U5") (pin "11") (pinfunction "GND_11") (pintype "passive"))
      (node (ref "U5") (pin "18") (pinfunction "GND_18") (pintype "passive"))
      (node (ref "U5") (pin "31") (pinfunction "GND_31") (pintype "passive"))
      (node (ref "U6") (pin "4") (pinfunction "VSS_4") (pintype "passive"))
      (node (ref "U7") (pin "1") (pinfunction "SDO_1") (pintype "passive"))
      (node (ref "U7") (pin "6") (pinfunction "GNDIO_6") (pintype "passive"))
      (node (ref "U7") (pin "7") (pinfunction "GND_7") (pintype "passive"))
    )
    (net (code "32") (name "Net-(BUZZER1--)") (class "Default")
      (node (ref "BUZZER1") (pin "2") (pinfunction "-_2") (pintype "passive"))
      (node (ref "D6") (pin "2") (pinfunction "A_2") (pintype "passive"))
      (node (ref "Q4") (pin "3") (pinfunction "D_3") (pintype "passive"))
    )
    (net (code "33") (name "Net-(D3-C)") (class "Default")
      (node (ref "D3") (pin "1") (pinfunction "C_1") (pintype "passive"))
      (node (ref "D4") (pin "1") (pinfunction "C_1") (pintype "passive"))
      (node (ref "SW1") (pin "2") (pinfunction "2_2") (pintype "passive"))
    )
    (net (code "34") (name "Net-(D4-A)") (class "Default")
      (node (ref "D4") (pin "2") (pinfunction "A_2") (pintype "passive"))
      (node (ref "Q2") (pin "1") (pinfunction "G_1") (pintype "passive"))
      (node (ref "Q3") (pin "3") (pinfunction "D_3") (pintype "passive"))
      (node (ref "R3") (pin "1") (pinfunction "1_1") (pintype "passive"))
    )
    (net (code "35") (name "Net-(LED1-A)") (class "Default")
      (node (ref "LED1") (pin "2") (pinfunction "A_2") (pintype "passive"))
      (node (ref "R1") (pin "2") (pinfunction "2_2") (pintype "passive"))
    )
    (net (code "36") (name "Net-(LED1-C)") (class "Default")
      (node (ref "LED1") (pin "1") (pinfunction "C_1") (pintype "passive"))
      (node (ref "U3") (pin "7") (pinfunction "CHRG#_7") (pintype "passive"))
    )
    (net (code "37") (name "Net-(LED2-A)") (class "Default")
      (node (ref "LED2") (pin "2") (pinfunction "A_2") (pintype "passive"))
      (node (ref "R18") (pin "2") (pinfunction "2_2") (pintype "passive"))
    )
    (net (code "38") (name "Net-(LED2-C)") (class "Default")
      (node (ref "LED2") (pin "1") (pinfunction "C_1") (pintype "passive"))
      (node (ref "U3") (pin "6") (pinfunction "STDBY#_6") (pintype "passive"))
    )
    (net (code "39") (name "Net-(Q1-G)") (class "Default")
      (node (ref "Q1") (pin "1") (pinfunction "G_1") (pintype "passive"))
      (node (ref "R2") (pin "2") (pinfunction "2_2") (pintype "passive"))
      (node (ref "U1") (pin "2") (pinfunction "RESET#_2") (pintype "passive"))
    )
    (net (code "40") (name "Net-(Q1-S)") (class "Default")
      (node (ref "C6") (pin "2") (pinfunction "2_2") (pintype "passive"))
      (node (ref "Q1") (pin "2") (pinfunction "S_2") (pintype "passive"))
      (node (ref "Q2") (pin "2") (pinfunction "S_2") (pintype "passive"))
      (node (ref "R3") (pin "2") (pinfunction "2_2") (pintype "passive"))
    )
    (net (code "41") (name "Net-(Q5-D)") (class "Default")
      (node (ref "Q5") (pin "3") (pinfunction "D_3") (pintype "passive"))
      (node (ref "R15") (pin "1") (pinfunction "1_1") (pintype "passive"))
    )
    (net (code "42") (name "Net-(U3-PROG)") (class "Default")
      (node (ref "R5") (pin "2") (pinfunction "2_2") (pintype "passive"))
      (node (ref "U3") (pin "2") (pinfunction "PROG_2") (pintype "passive"))
    )
    (net (code "43") (name "Net-(U6-OSCI)") (class "Default")
      (node (ref "C18") (pin "2") (pinfunction "2_2") (pintype "passive"))
      (node (ref "U6") (pin "1") (pinfunction "OSCI_1") (pintype "passive"))
      (node (ref "X1") (pin "1") (pinfunction "1_1") (pintype "passive"))
    )
    (net (code "44") (name "Net-(U6-OSCO)") (class "Default")
      (node (ref "C19") (pin "2") (pinfunction "2_2") (pintype "passive"))
      (node (ref "U6") (pin "2") (pinfunction "OSCO_2") (pintype "passive"))
      (node (ref "X1") (pin "2") (pinfunction "2_2") (pintype "passive"))
    )
    (net (code "45") (name "VBAT") (class "Default")
      (node (ref "C2") (pin "2") (pinfunction "2_2") (pintype "passive"))
      (node (ref "C3") (pin "2") (pinfunction "2_2") (pintype "passive"))
      (node (ref "C4") (pin "2") (pinfunction "2_2") (pintype "passive"))
      (node (ref "C8") (pin "2") (pinfunction "2_2") (pintype "passive"))
      (node (ref "D5") (pin "1") (pinfunction "K_1") (pintype "passive"))
      (node (ref "Q2") (pin "3") (pinfunction "D_3") (pintype "passive"))
      (node (ref "U2") (pin "1") (pinfunction "VIN_1") (pintype "passive"))
      (node (ref "U2") (pin "3") (pinfunction "EN_3") (pintype "passive"))
    )
    (net (code "46") (name "VBUS") (class "Default")
      (node (ref "C1") (pin "2") (pinfunction "2_2") (pintype "passive"))
      (node (ref "C5") (pin "1") (pinfunction "1_1") (pintype "passive"))
      (node (ref "D5") (pin "2") (pinfunction "A_2") (pintype "passive"))
      (node (ref "R1") (pin "1") (pinfunction "1_1") (pintype "passive"))
      (node (ref "R18") (pin "1") (pinfunction "1_1") (pintype "passive"))
      (node (ref "U1") (pin "3") (pinfunction "VCC_3") (pintype "passive"))
      (node (ref "U3") (pin "4") (pinfunction "VCC_4") (pintype "passive"))
      (node (ref "U3") (pin "8") (pinfunction "CE_8") (pintype "passive"))
      (node (ref "U5") (pin "13") (pinfunction "5V_13") (pintype "passive"))
    )
    (net (code "47") (name "VDD3V3") (class "Default")
      (node (ref "BUZZER1") (pin "1") (pinfunction "+_1") (pintype "passive"))
      (node (ref "C10") (pin "2") (pinfunction "2_2") (pintype "passive"))
      (node (ref "C20") (pin "2") (pinfunction "2_2") (pintype "passive"))
      (node (ref "C22") (pin "2") (pinfunction "2_2") (pintype "passive"))
      (node (ref "C23") (pin "2") (pinfunction "2_2") (pintype "passive"))
      (node (ref "C7") (pin "2") (pinfunction "2_2") (pintype "passive"))
      (node (ref "C9") (pin "2") (pinfunction "2_2") (pintype "passive"))
      (node (ref "CARD1") (pin "4") (pinfunction "VDD_4") (pintype "passive"))
      (node (ref "D6") (pin "1") (pinfunction "K_1") (pintype "passive"))
      (node (ref "M1") (pin "3") (pinfunction "LEDA_3") (pintype "passive"))
      (node (ref "M1") (pin "4") (pinfunction "VDD_4") (pintype "passive"))
      (node (ref "R10") (pin "2") (pinfunction "2_2") (pintype "passive"))
      (node (ref "R11") (pin "2") (pinfunction "2_2") (pintype "passive"))
      (node (ref "R16") (pin "2") (pinfunction "2_2") (pintype "passive"))
      (node (ref "R17") (pin "2") (pinfunction "2_2") (pintype "passive"))
      (node (ref "R8") (pin "2") (pinfunction "2_2") (pintype "passive"))
      (node (ref "R9") (pin "2") (pinfunction "2_2") (pintype "passive"))
      (node (ref "U2") (pin "5") (pinfunction "VOUT_5") (pintype "passive"))
      (node (ref "U5") (pin "28") (pinfunction "3V3_28") (pintype "passive"))
      (node (ref "U7") (pin "12") (pinfunction "CSB_12") (pintype "passive"))
      (node (ref "U7") (pin "5") (pinfunction "VDDIO_5") (pintype "passive"))
      (node (ref "U7") (pin "8") (pinfunction "VDD_8") (pintype "passive"))
    )
    (net (code "48") (name "unconnected-(CARD1-DAT1(RSV)-Pad8)") (class "Default")
      (node (ref "CARD1") (pin "8") (pinfunction "DAT1(RSV)_8") (pintype "passive+no_connect"))
    )
    (net (code "49") (name "unconnected-(CARD1-DAT2(RSV)-Pad1)") (class "Default")
      (node (ref "CARD1") (pin "1") (pinfunction "DAT2(RSV)_1") (pintype "passive+no_connect"))
    )
    (net (code "50") (name "unconnected-(SW2-EH-Pad7)") (class "Default")
      (node (ref "SW2") (pin "7") (pinfunction "EH_7") (pintype "passive"))
    )
    (net (code "51") (name "unconnected-(U2-NC-Pad4)") (class "Default")
      (node (ref "U2") (pin "4") (pinfunction "NC_4") (pintype "passive+no_connect"))
    )
    (net (code "52") (name "unconnected-(U6-CLKOUT-Pad7)") (class "Default")
      (node (ref "U6") (pin "7") (pinfunction "CLKOUT_7") (pintype "passive+no_connect"))
    )
    (net (code "53") (name "unconnected-(U7-ASCX-Pad3)") (class "Default")
      (node (ref "U7") (pin "3") (pinfunction "ASCX_3") (pintype "passive+no_connect"))
    )
    (net (code "54") (name "unconnected-(U7-ASDX-Pad2)") (class "Default")
      (node (ref "U7") (pin "2") (pinfunction "ASDX_2") (pintype "passive+no_connect"))
    )
    (net (code "55") (name "unconnected-(U7-OCSB-Pad10)") (class "Default")
      (node (ref "U7") (pin "10") (pinfunction "OCSB_10") (pintype "passive+no_connect"))
    )
    (net (code "56") (name "unconnected-(U7-OSDO-Pad11)") (class "Default")
      (node (ref "U7") (pin "11") (pinfunction "OSDO_11") (pintype "passive+no_connect"))
    )
  )
)
